# Gecko_IO.net
KiCad netlist of a schematic drawn in Altium Designer
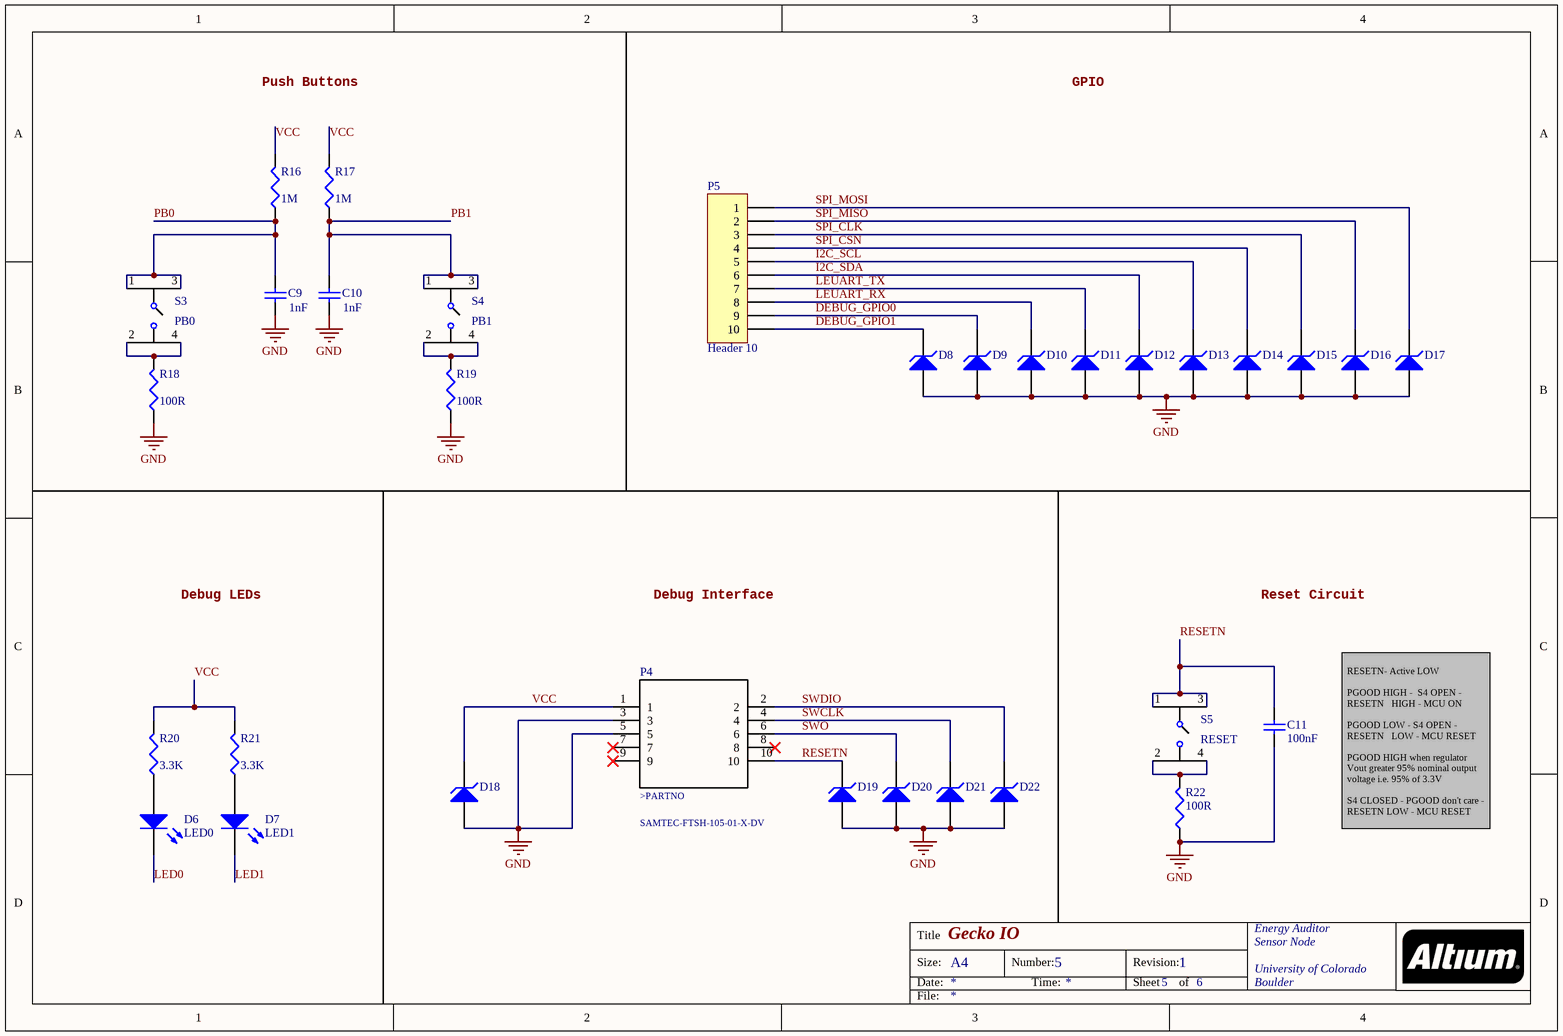
[diagram p0: Gecko IO.SchDoc]

(export (version "E")
  (design (tool "Eeschema 10.0.6"))
  (components
    (comp (ref "C9")
      (value "1nF")
      (footprint "1608[0603]")
      (description "CAP CER 1000PF 50V X7R 0603")
      (fields
        (field (name "DIGI-KEY PART NUMBER") "478-5006-1-ND")
        (field (name "MANUFACTURER") "AVX Corporation")
      )
      (libsource (lib "Miscellaneous Devices") (part "Cap"))
    )
    (comp (ref "C10")
      (value "1nF")
      (footprint "1608[0603]")
      (description "CAP CER 1000PF 50V X7R 0603")
      (fields
        (field (name "DIGI-KEY PART NUMBER") "478-5006-1-ND")
        (field (name "MANUFACTURER") "AVX Corporation")
      )
      (libsource (lib "Miscellaneous Devices") (part "Cap"))
    )
    (comp (ref "C11")
      (value "100nF")
      (footprint "1608[0603]")
      (description "CAP CER 0.1UF 16V X7R 0603")
      (fields
        (field (name "DIGI-KEY PART NUMBER") "478-7617-1-ND")
        (field (name "MANUFACTURER") "AVX Corporation")
      )
      (libsource (lib "Miscellaneous Devices") (part "Cap"))
    )
    (comp (ref "D6")
      (value "LED0")
      (footprint "3.2X1.6X1.1")
      (description "LED GREEN DIFFUSED 0603 SMD")
      (fields
        (field (name "DIGI-KEY PART NUMBER") "475-3118-1-ND")
        (field (name "MANUFACTURER") "OSRAM Opto Semiconductors Inc.")
      )
      (libsource (lib "Miscellaneous Devices") (part "LED2"))
    )
    (comp (ref "D7")
      (value "LED1")
      (footprint "3.2X1.6X1.1")
      (description "LED GREEN DIFFUSED 0603 SMD")
      (fields
        (field (name "DIGI-KEY PART NUMBER") "475-3118-1-ND")
        (field (name "MANUFACTURER") "OSRAM Opto Semiconductors Inc.")
      )
      (libsource (lib "Miscellaneous Devices") (part "LED2"))
    )
    (comp (ref "D8")
      (value "D Zener")
      (footprint "0402")
      (description "TVS DIODE 5.5V 14V 2X1SON")
      (fields
        (field (name "MANUFACTURER PART NUMBER") "TPD1E10B06DPYR")
        (field (name "DIGI-KEY PART NUMBER") "296-30406-1-ND")
      )
      (libsource (lib "Miscellaneous Devices") (part "D Zener"))
    )
    (comp (ref "D9")
      (value "D Zener")
      (footprint "0402")
      (description "TVS DIODE 5.5V 14V 2X1SON")
      (fields
        (field (name "MANUFACTURER PART NUMBER") "TPD1E10B06DPYR")
        (field (name "DIGI-KEY PART NUMBER") "296-30406-1-ND")
      )
      (libsource (lib "Miscellaneous Devices") (part "D Zener"))
    )
    (comp (ref "D10")
      (value "D Zener")
      (footprint "0402")
      (description "TVS DIODE 5.5V 14V 2X1SON")
      (fields
        (field (name "MANUFACTURER PART NUMBER") "TPD1E10B06DPYR")
        (field (name "DIGI-KEY PART NUMBER") "296-30406-1-ND")
      )
      (libsource (lib "Miscellaneous Devices") (part "D Zener"))
    )
    (comp (ref "D11")
      (value "D Zener")
      (footprint "0402")
      (description "TVS DIODE 5.5V 14V 2X1SON")
      (fields
        (field (name "MANUFACTURER PART NUMBER") "TPD1E10B06DPYR")
        (field (name "DIGI-KEY PART NUMBER") "296-30406-1-ND")
      )
      (libsource (lib "Miscellaneous Devices") (part "D Zener"))
    )
    (comp (ref "D12")
      (value "D Zener")
      (footprint "0402")
      (description "TVS DIODE 5.5V 14V 2X1SON")
      (fields
        (field (name "MANUFACTURER PART NUMBER") "TPD1E10B06DPYR")
        (field (name "DIGI-KEY PART NUMBER") "296-30406-1-ND")
      )
      (libsource (lib "Miscellaneous Devices") (part "D Zener"))
    )
    (comp (ref "D13")
      (value "D Zener")
      (footprint "0402")
      (description "TVS DIODE 5.5V 14V 2X1SON")
      (fields
        (field (name "MANUFACTURER PART NUMBER") "TPD1E10B06DPYR")
        (field (name "DIGI-KEY PART NUMBER") "296-30406-1-ND")
      )
      (libsource (lib "Miscellaneous Devices") (part "D Zener"))
    )
    (comp (ref "D14")
      (value "D Zener")
      (footprint "0402")
      (description "TVS DIODE 5.5V 14V 2X1SON")
      (fields
        (field (name "MANUFACTURER PART NUMBER") "TPD1E10B06DPYR")
        (field (name "DIGI-KEY PART NUMBER") "296-30406-1-ND")
      )
      (libsource (lib "Miscellaneous Devices") (part "D Zener"))
    )
    (comp (ref "D15")
      (value "D Zener")
      (footprint "0402")
      (description "TVS DIODE 5.5V 14V 2X1SON")
      (fields
        (field (name "MANUFACTURER PART NUMBER") "TPD1E10B06DPYR")
        (field (name "DIGI-KEY PART NUMBER") "296-30406-1-ND")
      )
      (libsource (lib "Miscellaneous Devices") (part "D Zener"))
    )
    (comp (ref "D16")
      (value "D Zener")
      (footprint "0402")
      (description "TVS DIODE 5.5V 14V 2X1SON")
      (fields
        (field (name "MANUFACTURER PART NUMBER") "TPD1E10B06DPYR")
        (field (name "DIGI-KEY PART NUMBER") "296-30406-1-ND")
      )
      (libsource (lib "Miscellaneous Devices") (part "D Zener"))
    )
    (comp (ref "D17")
      (value "D Zener")
      (footprint "0402")
      (description "TVS DIODE 5.5V 14V 2X1SON")
      (fields
        (field (name "MANUFACTURER PART NUMBER") "TPD1E10B06DPYR")
        (field (name "DIGI-KEY PART NUMBER") "296-30406-1-ND")
      )
      (libsource (lib "Miscellaneous Devices") (part "D Zener"))
    )
    (comp (ref "D18")
      (value "D Zener")
      (footprint "0402")
      (description "TVS DIODE 5.5V 14V 2X1SON")
      (fields
        (field (name "MANUFACTURER PART NUMBER") "TPD1E10B06DPYR")
        (field (name "DIGI-KEY PART NUMBER") "296-30406-1-ND")
      )
      (libsource (lib "Miscellaneous Devices") (part "D Zener"))
    )
    (comp (ref "D19")
      (value "D Zener")
      (footprint "0402")
      (description "TVS DIODE 5.5V 14V 2X1SON")
      (fields
        (field (name "MANUFACTURER PART NUMBER") "TPD1E10B06DPYR")
        (field (name "DIGI-KEY PART NUMBER") "296-30406-1-ND")
      )
      (libsource (lib "Miscellaneous Devices") (part "D Zener"))
    )
    (comp (ref "D20")
      (value "D Zener")
      (footprint "0402")
      (description "TVS DIODE 5.5V 14V 2X1SON")
      (fields
        (field (name "MANUFACTURER PART NUMBER") "TPD1E10B06DPYR")
        (field (name "DIGI-KEY PART NUMBER") "296-30406-1-ND")
      )
      (libsource (lib "Miscellaneous Devices") (part "D Zener"))
    )
    (comp (ref "D21")
      (value "D Zener")
      (footprint "0402")
      (description "TVS DIODE 5.5V 14V 2X1SON")
      (fields
        (field (name "MANUFACTURER PART NUMBER") "TPD1E10B06DPYR")
        (field (name "DIGI-KEY PART NUMBER") "296-30406-1-ND")
      )
      (libsource (lib "Miscellaneous Devices") (part "D Zener"))
    )
    (comp (ref "D22")
      (value "D Zener")
      (footprint "0402")
      (description "TVS DIODE 5.5V 14V 2X1SON")
      (fields
        (field (name "MANUFACTURER PART NUMBER") "TPD1E10B06DPYR")
        (field (name "DIGI-KEY PART NUMBER") "296-30406-1-ND")
      )
      (libsource (lib "Miscellaneous Devices") (part "D Zener"))
    )
    (comp (ref "P4")
      (value "SAMTEC-FTSH-105-01-X-DV")
      (footprint "SAMTEC-FTSH-105-01-X-DV")
      (description ".050\" X .050 TERMINAL STRIP")
      (fields
        (field (name "MANUFACTURER") "Samtec")
        (field (name "MANUFACTURER PART NUMBER") "FTSH-105-01-F-DV-K-TR")
      )
      (libsource (lib "Debug_connector") (part "SAMTEC-FTSH-105-01-X-DV"))
    )
    (comp (ref "P5")
      (value "Header 10")
      (footprint "HDR1X10")
      (description "Header, 10-Pin")
      (libsource (lib "Miscellaneous Connectors") (part "Header 10"))
    )
    (comp (ref "R16")
      (value "1M")
      (footprint "1608[0603]")
      (description "RES SMD 1M OHM 5% 1/10W 0603")
      (fields
        (field (name "DIGI-KEY PART NUMBER") "1276-5134-1-ND")
        (field (name "MANUFACTURER") "Samsung Electro-Mechanics")
      )
      (libsource (lib "Miscellaneous Devices") (part "Res3"))
    )
    (comp (ref "R17")
      (value "1M")
      (footprint "1608[0603]")
      (description "RES SMD 1M OHM 5% 1/10W 0603")
      (fields
        (field (name "DIGI-KEY PART NUMBER") "1276-5134-1-ND")
        (field (name "MANUFACTURER") "Samsung Electro-Mechanics")
      )
      (libsource (lib "Miscellaneous Devices") (part "Res3"))
    )
    (comp (ref "R18")
      (value "100R")
      (footprint "1608[0603]")
      (description "RES SMD 100 OHM 5% 1/10W 0603")
      (fields
        (field (name "DIGI-KEY PART NUMBER") "541-4059-1-ND")
        (field (name "MANUFACTURER") "Vishay Dale")
      )
      (libsource (lib "Miscellaneous Devices") (part "Res3"))
    )
    (comp (ref "R19")
      (value "100R")
      (footprint "1608[0603]")
      (description "RES SMD 100 OHM 5% 1/10W 0603")
      (fields
        (field (name "DIGI-KEY PART NUMBER") "541-4059-1-ND")
        (field (name "MANUFACTURER") "Vishay Dale")
      )
      (libsource (lib "Miscellaneous Devices") (part "Res3"))
    )
    (comp (ref "R20")
      (value "3.3K")
      (footprint "1608[0603]")
      (description "RES SMD 3.3K OHM 5% 1/10W 0603")
      (fields
        (field (name "DIGI-KEY PART NUMBER") "P3.3KGCT-ND")
        (field (name "MANUFACTURER") "Panasonic Electronic Components")
      )
      (libsource (lib "Miscellaneous Devices") (part "Res3"))
    )
    (comp (ref "R21")
      (value "3.3K")
      (footprint "1608[0603]")
      (description "RES SMD 3.3K OHM 5% 1/10W 0603")
      (fields
        (field (name "DIGI-KEY PART NUMBER") "P3.3KGCT-ND")
        (field (name "MANUFACTURER") "Panasonic Electronic Components")
      )
      (libsource (lib "Miscellaneous Devices") (part "Res3"))
    )
    (comp (ref "R22")
      (value "100R")
      (footprint "1608[0603]")
      (description "RES SMD 100 OHM 5% 1/10W 0603")
      (fields
        (field (name "DIGI-KEY PART NUMBER") "541-4059-1-ND")
        (field (name "MANUFACTURER") "Vishay Dale")
      )
      (libsource (lib "Miscellaneous Devices") (part "Res3"))
    )
    (comp (ref "S3")
      (value "PB0")
      (footprint "430182043816")
      (description "SWITCH TACTILE SPST-NO 0.05A 12V")
      (fields
        (field (name "MANUFACTURER PART NUMBER") "430182043816")
        (field (name "MANUFACTURER") "Wurth Electronics")
      )
      (libsource (lib "430182043816") (part "430182043816"))
    )
    (comp (ref "S4")
      (value "PB1")
      (footprint "430182043816")
      (description "SWITCH TACTILE SPST-NO 0.05A 12V")
      (fields
        (field (name "MANUFACTURER PART NUMBER") "430182043816")
        (field (name "MANUFACTURER") "Wurth Electronics")
      )
      (libsource (lib "430182043816") (part "430182043816"))
    )
    (comp (ref "S5")
      (value "RESET")
      (footprint "430182043816")
      (description "SWITCH TACTILE SPST-NO 0.05A 12V")
      (fields
        (field (name "MANUFACTURER PART NUMBER") "430182043816")
        (field (name "MANUFACTURER") "Wurth Electronics")
      )
      (libsource (lib "430182043816") (part "430182043816"))
    )
  )
  (nets
    (net (code "1") (name "/DEBUG_GPIO0") (class "Default")
      (node (ref "D9") (pin "2") (pinfunction "K_2") (pintype "passive"))
      (node (ref "P5") (pin "9") (pinfunction "9_9") (pintype "passive"))
    )
    (net (code "2") (name "/DEBUG_GPIO1") (class "Default")
      (node (ref "D8") (pin "2") (pinfunction "K_2") (pintype "passive"))
      (node (ref "P5") (pin "10") (pinfunction "10_10") (pintype "passive"))
    )
    (net (code "3") (name "/I2C_SCL") (class "Default")
      (node (ref "D13") (pin "2") (pinfunction "K_2") (pintype "passive"))
      (node (ref "P5") (pin "5") (pinfunction "5_5") (pintype "passive"))
    )
    (net (code "4") (name "/I2C_SDA") (class "Default")
      (node (ref "D12") (pin "2") (pinfunction "K_2") (pintype "passive"))
      (node (ref "P5") (pin "6") (pinfunction "6_6") (pintype "passive"))
    )
    (net (code "5") (name "/LED0") (class "Default")
      (node (ref "D6") (pin "2") (pinfunction "K_2") (pintype "passive"))
    )
    (net (code "6") (name "/LED1") (class "Default")
      (node (ref "D7") (pin "2") (pinfunction "K_2") (pintype "passive"))
    )
    (net (code "7") (name "/LEUART_RX") (class "Default")
      (node (ref "D10") (pin "2") (pinfunction "K_2") (pintype "passive"))
      (node (ref "P5") (pin "8") (pinfunction "8_8") (pintype "passive"))
    )
    (net (code "8") (name "/LEUART_TX") (class "Default")
      (node (ref "D11") (pin "2") (pinfunction "K_2") (pintype "passive"))
      (node (ref "P5") (pin "7") (pinfunction "7_7") (pintype "passive"))
    )
    (net (code "9") (name "/PB0") (class "Default")
      (node (ref "C9") (pin "2") (pinfunction "2_2") (pintype "passive"))
      (node (ref "R16") (pin "1") (pinfunction "1_1") (pintype "passive"))
      (node (ref "S3") (pin "1") (pinfunction "1_1") (pintype "passive"))
      (node (ref "S3") (pin "3") (pinfunction "3_3") (pintype "passive"))
    )
    (net (code "10") (name "/PB1") (class "Default")
      (node (ref "C10") (pin "2") (pinfunction "2_2") (pintype "passive"))
      (node (ref "R17") (pin "1") (pinfunction "1_1") (pintype "passive"))
      (node (ref "S4") (pin "1") (pinfunction "1_1") (pintype "passive"))
      (node (ref "S4") (pin "3") (pinfunction "3_3") (pintype "passive"))
    )
    (net (code "11") (name "/RESETN") (class "Default")
      (node (ref "C11") (pin "1") (pinfunction "1_1") (pintype "passive"))
      (node (ref "D19") (pin "2") (pinfunction "K_2") (pintype "passive"))
      (node (ref "P4") (pin "10") (pinfunction "10_10") (pintype "passive"))
      (node (ref "S5") (pin "1") (pinfunction "1_1") (pintype "passive"))
      (node (ref "S5") (pin "3") (pinfunction "3_3") (pintype "passive"))
    )
    (net (code "12") (name "/SPI_CLK") (class "Default")
      (node (ref "D15") (pin "2") (pinfunction "K_2") (pintype "passive"))
      (node (ref "P5") (pin "3") (pinfunction "3_3") (pintype "passive"))
    )
    (net (code "13") (name "/SPI_CSN") (class "Default")
      (node (ref "D14") (pin "2") (pinfunction "K_2") (pintype "passive"))
      (node (ref "P5") (pin "4") (pinfunction "4_4") (pintype "passive"))
    )
    (net (code "14") (name "/SPI_MISO") (class "Default")
      (node (ref "D16") (pin "2") (pinfunction "K_2") (pintype "passive"))
      (node (ref "P5") (pin "2") (pinfunction "2_2") (pintype "passive"))
    )
    (net (code "15") (name "/SPI_MOSI") (class "Default")
      (node (ref "D17") (pin "2") (pinfunction "K_2") (pintype "passive"))
      (node (ref "P5") (pin "1") (pinfunction "1_1") (pintype "passive"))
    )
    (net (code "16") (name "/SWCLK") (class "Default")
      (node (ref "D21") (pin "2") (pinfunction "K_2") (pintype "passive"))
      (node (ref "P4") (pin "4") (pinfunction "4_4") (pintype "passive"))
    )
    (net (code "17") (name "/SWDIO") (class "Default")
      (node (ref "D22") (pin "2") (pinfunction "K_2") (pintype "passive"))
      (node (ref "P4") (pin "2") (pinfunction "2_2") (pintype "passive"))
    )
    (net (code "18") (name "/SWO") (class "Default")
      (node (ref "D20") (pin "2") (pinfunction "K_2") (pintype "passive"))
      (node (ref "P4") (pin "6") (pinfunction "6_6") (pintype "passive"))
    )
    (net (code "19") (name "/VCC") (class "Default")
      (node (ref "D18") (pin "2") (pinfunction "K_2") (pintype "passive"))
      (node (ref "P4") (pin "1") (pinfunction "1_1") (pintype "passive"))
      (node (ref "R16") (pin "2") (pinfunction "2_2") (pintype "passive"))
      (node (ref "R17") (pin "2") (pinfunction "2_2") (pintype "passive"))
      (node (ref "R20") (pin "2") (pinfunction "2_2") (pintype "passive"))
      (node (ref "R21") (pin "2") (pinfunction "2_2") (pintype "passive"))
    )
    (net (code "20") (name "GND") (class "Default")
      (node (ref "C10") (pin "1") (pinfunction "1_1") (pintype "passive"))
      (node (ref "C11") (pin "2") (pinfunction "2_2") (pintype "passive"))
      (node (ref "C9") (pin "1") (pinfunction "1_1") (pintype "passive"))
      (node (ref "D10") (pin "1") (pinfunction "A_1") (pintype "passive"))
      (node (ref "D11") (pin "1") (pinfunction "A_1") (pintype "passive"))
      (node (ref "D12") (pin "1") (pinfunction "A_1") (pintype "passive"))
      (node (ref "D13") (pin "1") (pinfunction "A_1") (pintype "passive"))
      (node (ref "D14") (pin "1") (pinfunction "A_1") (pintype "passive"))
      (node (ref "D15") (pin "1") (pinfunction "A_1") (pintype "passive"))
      (node (ref "D16") (pin "1") (pinfunction "A_1") (pintype "passive"))
      (node (ref "D17") (pin "1") (pinfunction "A_1") (pintype "passive"))
      (node (ref "D18") (pin "1") (pinfunction "A_1") (pintype "passive"))
      (node (ref "D19") (pin "1") (pinfunction "A_1") (pintype "passive"))
      (node (ref "D20") (pin "1") (pinfunction "A_1") (pintype "passive"))
      (node (ref "D21") (pin "1") (pinfunction "A_1") (pintype "passive"))
      (node (ref "D22") (pin "1") (pinfunction "A_1") (pintype "passive"))
      (node (ref "D8") (pin "1") (pinfunction "A_1") (pintype "passive"))
      (node (ref "D9") (pin "1") (pinfunction "A_1") (pintype "passive"))
      (node (ref "P4") (pin "3") (pinfunction "3_3") (pintype "passive"))
      (node (ref "P4") (pin "5") (pinfunction "5_5") (pintype "passive"))
      (node (ref "R18") (pin "1") (pinfunction "1_1") (pintype "passive"))
      (node (ref "R19") (pin "1") (pinfunction "1_1") (pintype "passive"))
      (node (ref "R22") (pin "1") (pinfunction "1_1") (pintype "passive"))
    )
    (net (code "21") (name "Net-(D6-A)") (class "Default")
      (node (ref "D6") (pin "1") (pinfunction "A_1") (pintype "passive"))
      (node (ref "R20") (pin "1") (pinfunction "1_1") (pintype "passive"))
    )
    (net (code "22") (name "Net-(D7-A)") (class "Default")
      (node (ref "D7") (pin "1") (pinfunction "A_1") (pintype "passive"))
      (node (ref "R21") (pin "1") (pinfunction "1_1") (pintype "passive"))
    )
    (net (code "23") (name "Net-(R18-Pad2)") (class "Default")
      (node (ref "R18") (pin "2") (pinfunction "2_2") (pintype "passive"))
      (node (ref "S3") (pin "2") (pinfunction "2_2") (pintype "passive"))
      (node (ref "S3") (pin "4") (pinfunction "4_4") (pintype "passive"))
    )
    (net (code "24") (name "Net-(R19-Pad2)") (class "Default")
      (node (ref "R19") (pin "2") (pinfunction "2_2") (pintype "passive"))
      (node (ref "S4") (pin "2") (pinfunction "2_2") (pintype "passive"))
      (node (ref "S4") (pin "4") (pinfunction "4_4") (pintype "passive"))
    )
    (net (code "25") (name "Net-(R22-Pad2)") (class "Default")
      (node (ref "R22") (pin "2") (pinfunction "2_2") (pintype "passive"))
      (node (ref "S5") (pin "2") (pinfunction "2_2") (pintype "passive"))
      (node (ref "S5") (pin "4") (pinfunction "4_4") (pintype "passive"))
    )
    (net (code "26") (name "unconnected-(P4-Pad7)") (class "Default")
      (node (ref "P4") (pin "7") (pinfunction "7_7") (pintype "passive+no_connect"))
    )
    (net (code "27") (name "unconnected-(P4-Pad8)") (class "Default")
      (node (ref "P4") (pin "8") (pinfunction "8_8") (pintype "passive+no_connect"))
    )
    (net (code "28") (name "unconnected-(P4-Pad9)") (class "Default")
      (node (ref "P4") (pin "9") (pinfunction "9_9") (pintype "passive+no_connect"))
    )
  )
)
